# Mouse_Sensor_B3.net
KiCad netlist of a schematic drawn in Altium Designer
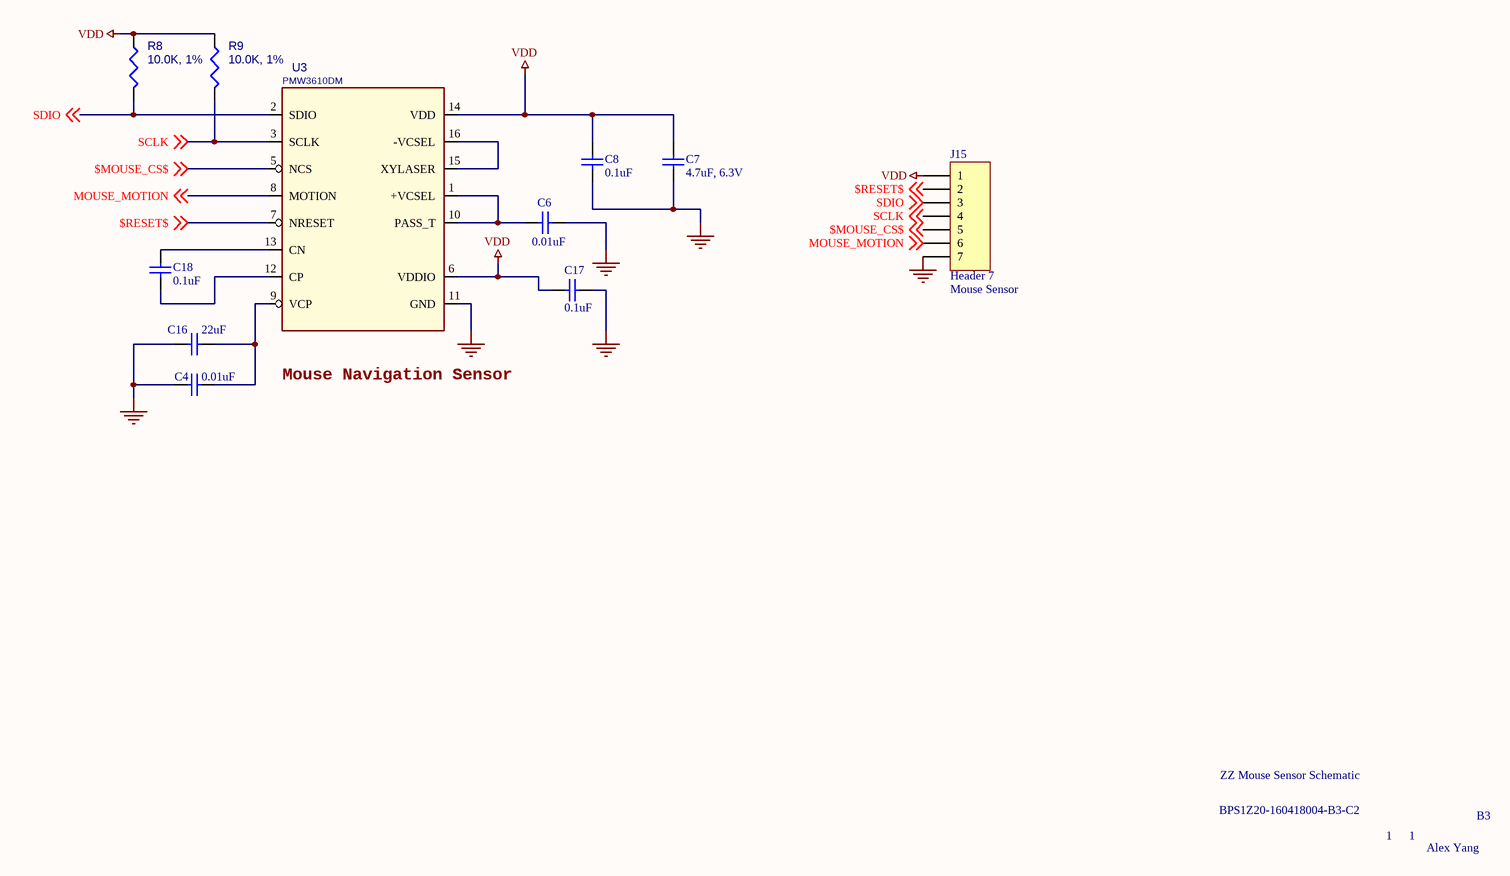
[diagram p0: Mouse Sensor B3.SchDoc]

(export (version "E")
  (design (tool "Eeschema 10.0.6"))
  (components
    (comp (ref "C4")
      (value "0.01uF")
      (footprint "RAD-0.3")
      (description "Capacitor")
      (fields (field (name "PUBLISHER") "Altium Limited"))
      (libsource (lib "Miscellaneous Devices") (part "Cap"))
    )
    (comp (ref "C6")
      (value "0.01uF")
      (footprint "RAD-0.3")
      (description "Capacitor")
      (fields (field (name "PUBLISHER") "Altium Limited"))
      (libsource (lib "Miscellaneous Devices") (part "Cap"))
    )
    (comp (ref "C7")
      (value "4.7uF, 6.3V")
      (footprint "RAD-0.3")
      (description "Capacitor")
      (fields (field (name "PUBLISHER") "Altium Limited"))
      (libsource (lib "Miscellaneous Devices") (part "Cap"))
    )
    (comp (ref "C8")
      (value "0.1uF")
      (footprint "RAD-0.3")
      (description "Capacitor")
      (fields (field (name "PUBLISHER") "Altium Limited"))
      (libsource (lib "Miscellaneous Devices") (part "Cap"))
    )
    (comp (ref "C16")
      (value "22uF")
      (footprint "RAD-0.3")
      (description "Capacitor")
      (fields (field (name "PUBLISHER") "Altium Limited"))
      (libsource (lib "Miscellaneous Devices") (part "Cap"))
    )
    (comp (ref "C17")
      (value "0.1uF")
      (footprint "RAD-0.3")
      (description "Capacitor")
      (fields (field (name "PUBLISHER") "Altium Limited"))
      (libsource (lib "Miscellaneous Devices") (part "Cap"))
    )
    (comp (ref "C18")
      (value "0.1uF")
      (footprint "RAD-0.3")
      (description "Capacitor")
      (fields (field (name "PUBLISHER") "Altium Limited"))
      (libsource (lib "Miscellaneous Devices") (part "Cap"))
    )
    (comp (ref "J15")
      (value "Header 7")
      (footprint "HDR1X7h")
      (description "Header, 7-Pin")
      (fields (field (name "PUBLISHER") "Altium Limited"))
      (libsource (lib "Miscellaneous Connectors") (part "Header 7"))
    )
    (comp (ref "R8") (value "10.0K, 1%") (footprint "0402") (libsource (lib "*") (part "R")))
    (comp (ref "R9") (value "10.0K, 1%") (footprint "0402") (libsource (lib "*") (part "R")))
    (comp (ref "U3")
      (value "PMW3610DM")
      (footprint "PMW_3610_DIP16")
      (libsource (lib "*") (part "PMW3610DM"))
    )
  )
  (nets
    (net (code "1") (name "$MOUSE_CS$") (class "Default")
      (node (ref "J15") (pin "5") (pinfunction "5_5") (pintype "passive"))
      (node (ref "U3") (pin "5") (pinfunction "NCS_5") (pintype "passive"))
    )
    (net (code "2") (name "$RESET$") (class "Default")
      (node (ref "J15") (pin "2") (pinfunction "2_2") (pintype "passive"))
      (node (ref "U3") (pin "7") (pinfunction "NRESET_7") (pintype "passive"))
    )
    (net (code "3") (name "GND") (class "Default")
      (node (ref "C16") (pin "1") (pinfunction "1_1") (pintype "passive"))
      (node (ref "C17") (pin "2") (pinfunction "2_2") (pintype "passive"))
      (node (ref "C4") (pin "1") (pinfunction "1_1") (pintype "passive"))
      (node (ref "C6") (pin "2") (pinfunction "2_2") (pintype "passive"))
      (node (ref "C7") (pin "1") (pinfunction "1_1") (pintype "passive"))
      (node (ref "C8") (pin "1") (pinfunction "1_1") (pintype "passive"))
      (node (ref "J15") (pin "7") (pinfunction "7_7") (pintype "passive"))
      (node (ref "U3") (pin "11") (pinfunction "GND_11") (pintype "passive"))
    )
    (net (code "4") (name "MOUSE_MOTION") (class "Default")
      (node (ref "J15") (pin "6") (pinfunction "6_6") (pintype "passive"))
      (node (ref "U3") (pin "8") (pinfunction "MOTION_8") (pintype "passive"))
    )
    (net (code "5") (name "Net-(U3-+VCSEL)") (class "Default")
      (node (ref "C6") (pin "1") (pinfunction "1_1") (pintype "passive"))
      (node (ref "U3") (pin "1") (pinfunction "+VCSEL_1") (pintype "passive"))
      (node (ref "U3") (pin "10") (pinfunction "PASS_T_10") (pintype "passive"))
    )
    (net (code "6") (name "Net-(U3--VCSEL)") (class "Default")
      (node (ref "U3") (pin "15") (pinfunction "XYLASER_15") (pintype "passive"))
      (node (ref "U3") (pin "16") (pinfunction "-VCSEL_16") (pintype "passive"))
    )
    (net (code "7") (name "Net-(U3-CN)") (class "Default")
      (node (ref "C18") (pin "2") (pinfunction "2_2") (pintype "passive"))
      (node (ref "U3") (pin "13") (pinfunction "CN_13") (pintype "passive"))
    )
    (net (code "8") (name "Net-(U3-CP)") (class "Default")
      (node (ref "C18") (pin "1") (pinfunction "1_1") (pintype "passive"))
      (node (ref "U3") (pin "12") (pinfunction "CP_12") (pintype "passive"))
    )
    (net (code "9") (name "Net-(U3-VCP)") (class "Default")
      (node (ref "C16") (pin "2") (pinfunction "2_2") (pintype "passive"))
      (node (ref "C4") (pin "2") (pinfunction "2_2") (pintype "passive"))
      (node (ref "U3") (pin "9") (pinfunction "VCP_9") (pintype "passive"))
    )
    (net (code "10") (name "SCLK") (class "Default")
      (node (ref "J15") (pin "4") (pinfunction "4_4") (pintype "passive"))
      (node (ref "R9") (pin "2") (pinfunction "2_2") (pintype "passive"))
      (node (ref "U3") (pin "3") (pinfunction "SCLK_3") (pintype "passive"))
    )
    (net (code "11") (name "SDIO") (class "Default")
      (node (ref "J15") (pin "3") (pinfunction "3_3") (pintype "passive"))
      (node (ref "R8") (pin "2") (pinfunction "2_2") (pintype "passive"))
      (node (ref "U3") (pin "2") (pinfunction "SDIO_2") (pintype "passive"))
    )
    (net (code "12") (name "VDD") (class "Default")
      (node (ref "C17") (pin "1") (pinfunction "1_1") (pintype "passive"))
      (node (ref "C7") (pin "2") (pinfunction "2_2") (pintype "passive"))
      (node (ref "C8") (pin "2") (pinfunction "2_2") (pintype "passive"))
      (node (ref "J15") (pin "1") (pinfunction "1_1") (pintype "passive"))
      (node (ref "R8") (pin "1") (pinfunction "1_1") (pintype "passive"))
      (node (ref "R9") (pin "1") (pinfunction "1_1") (pintype "passive"))
      (node (ref "U3") (pin "14") (pinfunction "VDD_14") (pintype "power_in"))
      (node (ref "U3") (pin "6") (pinfunction "VDDIO_6") (pintype "passive"))
    )
  )
)
